# BPU_display-v1d-20inch.net
KiCad netlist of a schematic drawn in EAGLE
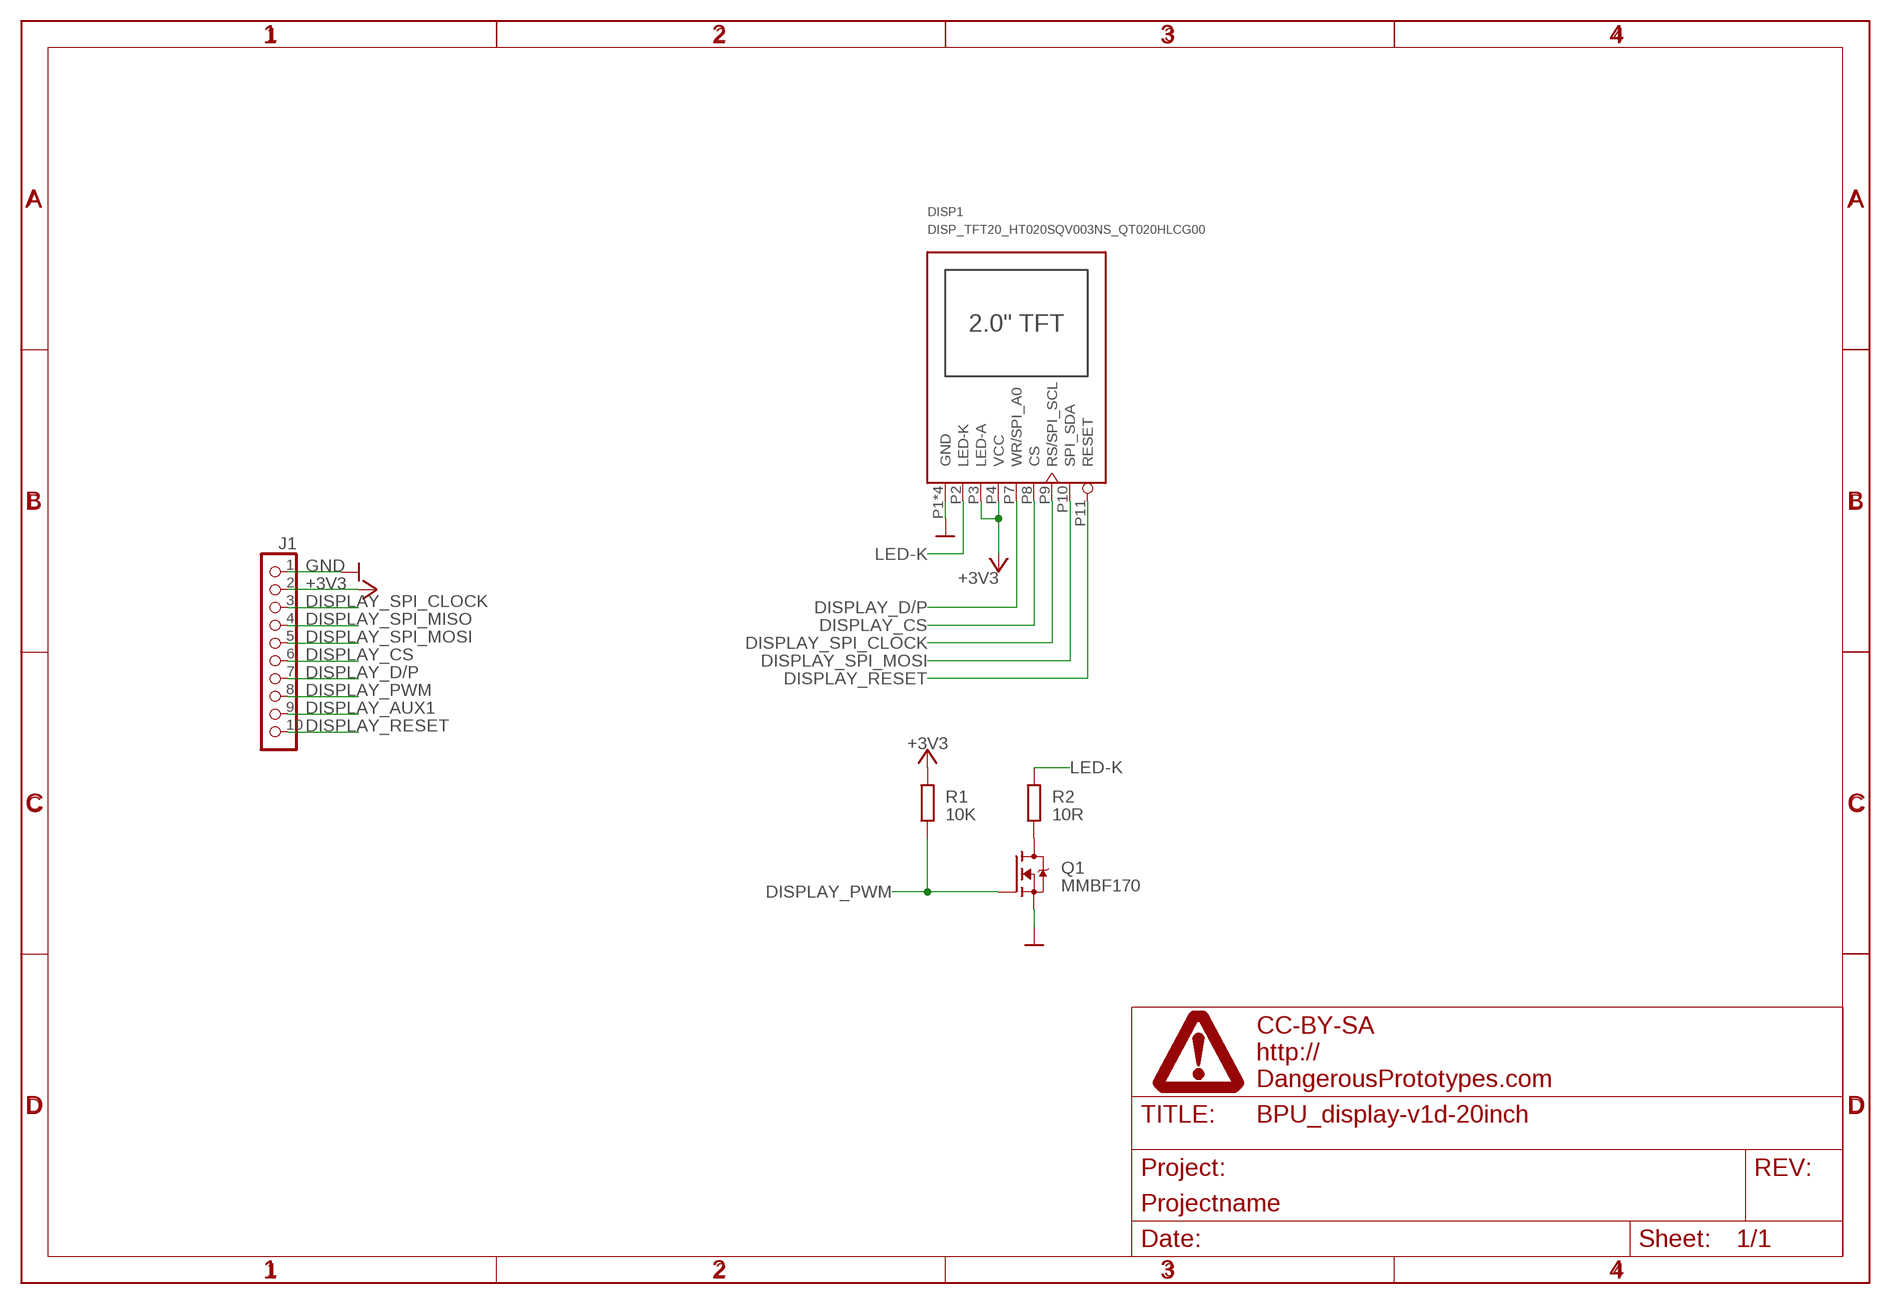
[diagram p0: schematic, sheet 1]

(export (version "E")
  (design (tool "Eeschema 10.0.6"))
  (components
    (comp (ref "DISP1")
      (value "DISP_TFT20_HT020SQV003NS_QT020HLCG00")
      (footprint "eagle-import:HT020SQV003NS_QT020HLCG00")
      (libsource (lib "eagle-import") (part "DISP_TFT20_HT020SQV003NS_QT020HLCG00"))
    )
    (comp (ref "J1")
      (value "CON-FPC_X05B20L10T")
      (footprint "eagle-import:X05B20L10T")
      (libsource (lib "eagle-import") (part "CON-FPC_X05B20L10T"))
    )
    (comp (ref "PAGE1")
      (value "FRAME_DINA4_L")
      (footprint "eagle-import:DP_LOGO")
      (fields
        (field (name "LICENSE") "CC-BY-SA")
        (field (name "URL1") "http://")
        (field (name "URL2") "DangerousPrototypes.com")
        (field (name "PROJECT") "Projectname")
      )
      (libsource (lib "eagle-import") (part "FRAME_DINA4_L"))
    )
    (comp (ref "Q1")
      (value "MMBF170")
      (footprint "eagle-import:SOT-23")
      (libsource (lib "eagle-import") (part "TRANSISTOR_FET_BS170-SOT-23"))
    )
    (comp (ref "R1")
      (value "10K")
      (footprint "eagle-import:R0603")
      (libsource (lib "eagle-import") (part "R-EU_R0603"))
    )
    (comp (ref "R2")
      (value "10R")
      (footprint "eagle-import:R0603")
      (libsource (lib "eagle-import") (part "R-EU_R0603"))
    )
  )
  (nets
    (net (code "1") (name "/DISPLAY_AUX1") (class "Default")
      (node (ref "J1") (pin "9") (pinfunction "9_9") (pintype "passive"))
    )
    (net (code "2") (name "/DISPLAY_CS") (class "Default")
      (node (ref "DISP1") (pin "P8") (pinfunction "CS_P8") (pintype "input"))
      (node (ref "J1") (pin "6") (pinfunction "6_6") (pintype "passive"))
    )
    (net (code "3") (name "/DISPLAY_D{slash}P") (class "Default")
      (node (ref "DISP1") (pin "P7") (pinfunction "WR/SPI_A0_P7") (pintype "input"))
      (node (ref "J1") (pin "7") (pinfunction "7_7") (pintype "passive"))
    )
    (net (code "4") (name "/DISPLAY_PWM") (class "Default")
      (node (ref "J1") (pin "8") (pinfunction "8_8") (pintype "passive"))
      (node (ref "Q1") (pin "1") (pinfunction "G_1") (pintype "passive"))
      (node (ref "R1") (pin "1") (pinfunction "1_1") (pintype "passive"))
    )
    (net (code "5") (name "/DISPLAY_RESET") (class "Default")
      (node (ref "DISP1") (pin "P11") (pinfunction "RESET_P11") (pintype "input"))
      (node (ref "J1") (pin "10") (pinfunction "10_10") (pintype "passive"))
    )
    (net (code "6") (name "/DISPLAY_SPI_CLOCK") (class "Default")
      (node (ref "DISP1") (pin "P9") (pinfunction "RS/SPI_SCL_P9") (pintype "input"))
      (node (ref "J1") (pin "3") (pinfunction "3_3") (pintype "passive"))
    )
    (net (code "7") (name "/DISPLAY_SPI_MISO") (class "Default")
      (node (ref "J1") (pin "4") (pinfunction "4_4") (pintype "passive"))
    )
    (net (code "8") (name "/DISPLAY_SPI_MOSI") (class "Default")
      (node (ref "DISP1") (pin "P10") (pinfunction "SPI_SDA_P10") (pintype "bidirectional"))
      (node (ref "J1") (pin "5") (pinfunction "5_5") (pintype "passive"))
    )
    (net (code "9") (name "/LED-K") (class "Default")
      (node (ref "DISP1") (pin "P2") (pinfunction "LED-K_P2") (pintype "power_in"))
      (node (ref "R2") (pin "2") (pinfunction "2_2") (pintype "passive"))
    )
    (net (code "10") (name "Net-(Q1-D)") (class "Default")
      (node (ref "Q1") (pin "3") (pinfunction "D_3") (pintype "passive"))
      (node (ref "R2") (pin "1") (pinfunction "1_1") (pintype "passive"))
    )
    (net (code "11") (name "SUPPLY_+3V3") (class "Default")
      (node (ref "DISP1") (pin "P3") (pinfunction "LED-A_P3") (pintype "power_in"))
      (node (ref "DISP1") (pin "P4") (pinfunction "VCC_P4") (pintype "power_in"))
      (node (ref "J1") (pin "2") (pinfunction "2_2") (pintype "passive"))
      (node (ref "R1") (pin "2") (pinfunction "2_2") (pintype "passive"))
    )
    (net (code "12") (name "SUPPLY_GND") (class "Default")
      (node (ref "DISP1") (pin "P1") (pinfunction "GND_P1") (pintype "power_in"))
      (node (ref "DISP1") (pin "P12") (pinfunction "GND_P12") (pintype "power_in"))
      (node (ref "DISP1") (pin "P5") (pinfunction "GND_P5") (pintype "power_in"))
      (node (ref "DISP1") (pin "P6") (pinfunction "GND_P6") (pintype "power_in"))
      (node (ref "J1") (pin "1") (pinfunction "1_1") (pintype "passive"))
      (node (ref "Q1") (pin "2") (pinfunction "S_2") (pintype "passive"))
    )
  )
)
